# Sensors.net
KiCad netlist of a schematic drawn in Altium Designer
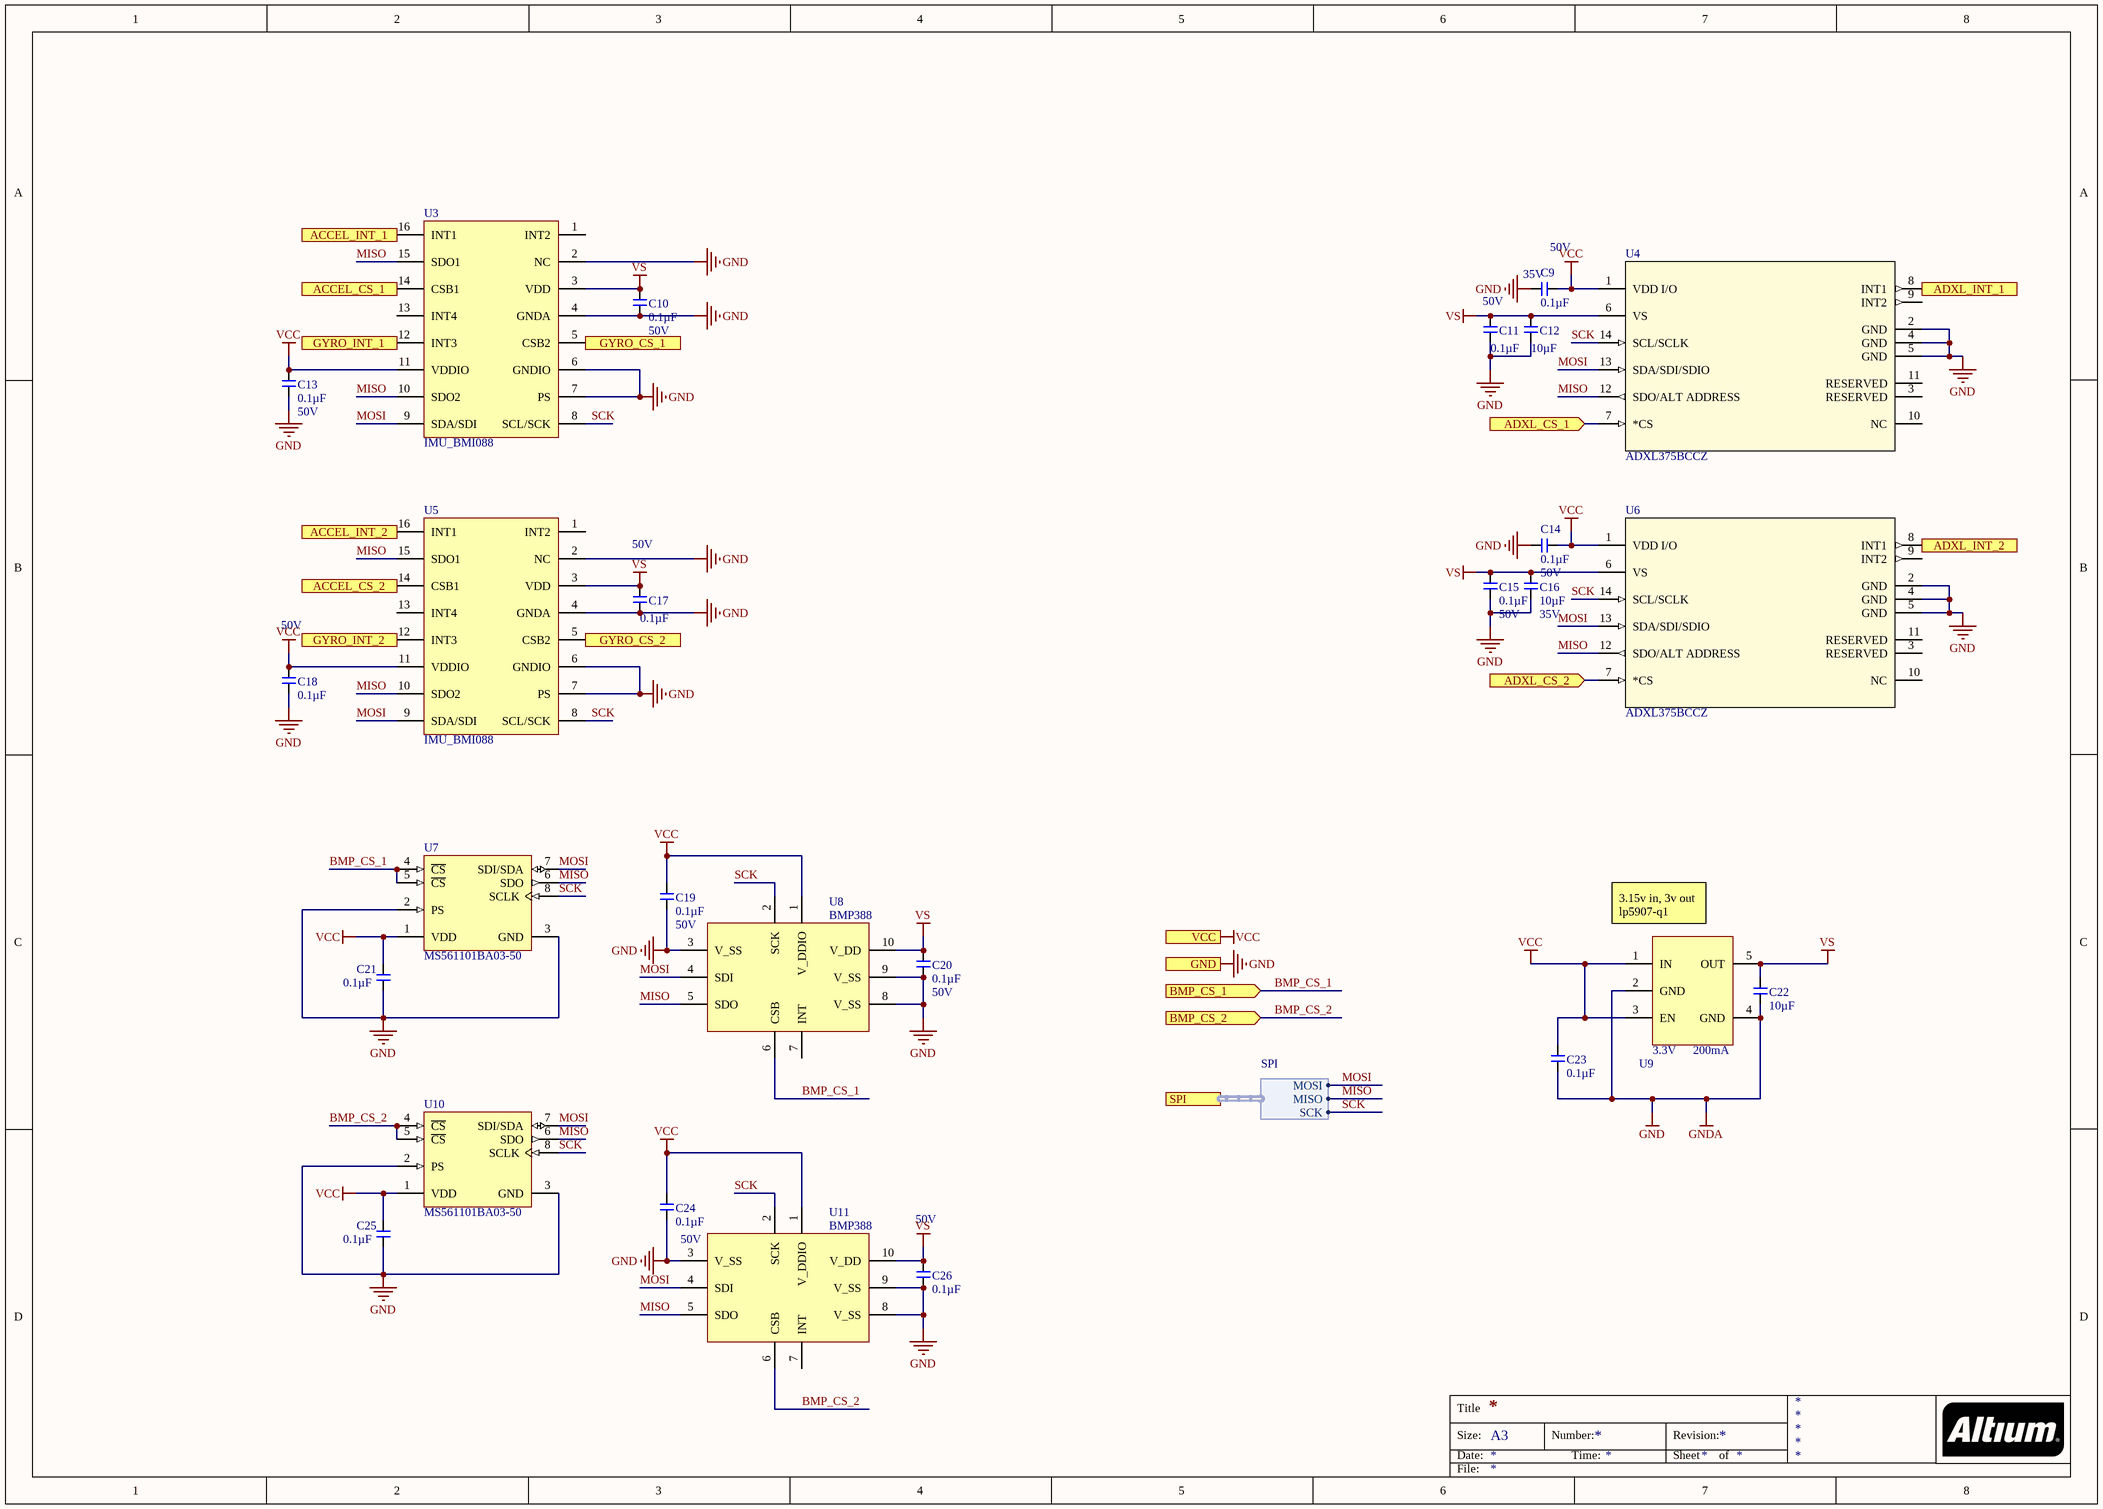
[diagram p0: Sensors.SchDoc]

(export (version "E")
  (design (tool "Eeschema 10.0.6"))
  (components
    (comp (ref "C9")
      (value "490-1519-1-ND")
      (footprint "C0603")
      (description "CAP CER 0603 0.1µF X7R 50V 10%")
      (fields
        (field (name "CAPACITANCE (SHORTHAND)") "0.1µF")
        (field (name "MANUFACTURER") "Murata Electronics North America")
        (field (name "RATED VOLTAGE") "50V")
      )
      (libsource (lib "Stanford Student Space Initiative") (part "__template_cap"))
    )
    (comp (ref "C10")
      (value "490-1519-1-ND")
      (footprint "C0603")
      (description "CAP CER 0603 0.1µF X7R 50V 10%")
      (fields
        (field (name "CAPACITANCE (SHORTHAND)") "0.1µF")
        (field (name "MANUFACTURER") "Murata Electronics North America")
        (field (name "RATED VOLTAGE") "50V")
      )
      (libsource (lib "Stanford Student Space Initiative") (part "__template_cap"))
    )
    (comp (ref "C11")
      (value "490-1519-1-ND")
      (footprint "C0603")
      (description "CAP CER 0603 0.1µF X7R 50V 10%")
      (fields
        (field (name "CAPACITANCE (SHORTHAND)") "0.1µF")
        (field (name "MANUFACTURER") "Murata Electronics North America")
        (field (name "RATED VOLTAGE") "50V")
      )
      (libsource (lib "Stanford Student Space Initiative") (part "__template_cap"))
    )
    (comp (ref "C12")
      (value "490-13248-1-ND")
      (footprint "C0603")
      (description "CAP CER 10UF 35V X5R 0603 20%")
      (fields
        (field (name "CAPACITANCE (SHORTHAND)") "10µF")
        (field (name "MANUFACTURER") "Murata Electronics North America")
        (field (name "RATED VOLTAGE") "35V")
      )
      (libsource (lib "Stanford Student Space Initiative") (part "__template_cap"))
    )
    (comp (ref "C13")
      (value "490-1519-1-ND")
      (footprint "C0603")
      (description "CAP CER 0603 0.1µF X7R 50V 10%")
      (fields
        (field (name "CAPACITANCE (SHORTHAND)") "0.1µF")
        (field (name "MANUFACTURER") "Murata Electronics North America")
        (field (name "RATED VOLTAGE") "50V")
      )
      (libsource (lib "Stanford Student Space Initiative") (part "__template_cap"))
    )
    (comp (ref "C14")
      (value "490-1519-1-ND")
      (footprint "C0603")
      (description "CAP CER 0603 0.1µF X7R 50V 10%")
      (fields
        (field (name "CAPACITANCE (SHORTHAND)") "0.1µF")
        (field (name "MANUFACTURER") "Murata Electronics North America")
        (field (name "RATED VOLTAGE") "50V")
      )
      (libsource (lib "Stanford Student Space Initiative") (part "__template_cap"))
    )
    (comp (ref "C15")
      (value "490-1519-1-ND")
      (footprint "C0603")
      (description "CAP CER 0603 0.1µF X7R 50V 10%")
      (fields
        (field (name "CAPACITANCE (SHORTHAND)") "0.1µF")
        (field (name "MANUFACTURER") "Murata Electronics North America")
        (field (name "RATED VOLTAGE") "50V")
      )
      (libsource (lib "Stanford Student Space Initiative") (part "__template_cap"))
    )
    (comp (ref "C16")
      (value "490-13248-1-ND")
      (footprint "C0603")
      (description "CAP CER 10UF 35V X5R 0603 20%")
      (fields
        (field (name "CAPACITANCE (SHORTHAND)") "10µF")
        (field (name "MANUFACTURER") "Murata Electronics North America")
        (field (name "RATED VOLTAGE") "35V")
      )
      (libsource (lib "Stanford Student Space Initiative") (part "__template_cap"))
    )
    (comp (ref "C17")
      (value "490-1519-1-ND")
      (footprint "C0603")
      (description "CAP CER 0603 0.1µF X7R 50V 10%")
      (fields
        (field (name "CAPACITANCE (SHORTHAND)") "0.1µF")
        (field (name "MANUFACTURER") "Murata Electronics North America")
        (field (name "RATED VOLTAGE") "50V")
      )
      (libsource (lib "Stanford Student Space Initiative") (part "__template_cap"))
    )
    (comp (ref "C18")
      (value "490-1519-1-ND")
      (footprint "C0603")
      (description "CAP CER 0603 0.1µF X7R 50V 10%")
      (fields
        (field (name "CAPACITANCE (SHORTHAND)") "0.1µF")
        (field (name "MANUFACTURER") "Murata Electronics North America")
        (field (name "RATED VOLTAGE") "50V")
      )
      (libsource (lib "Stanford Student Space Initiative") (part "__template_cap"))
    )
    (comp (ref "C19")
      (value "490-1519-1-ND")
      (footprint "C0603")
      (description "CAP CER 0603 0.1µF X7R 50V 10%")
      (fields
        (field (name "CAPACITANCE (SHORTHAND)") "0.1µF")
        (field (name "MANUFACTURER") "Murata Electronics North America")
        (field (name "RATED VOLTAGE") "50V")
      )
      (libsource (lib "Stanford Student Space Initiative") (part "__template_cap"))
    )
    (comp (ref "C20")
      (value "490-1519-1-ND")
      (footprint "C0603")
      (description "CAP CER 0603 0.1µF X7R 50V 10%")
      (fields
        (field (name "CAPACITANCE (SHORTHAND)") "0.1µF")
        (field (name "MANUFACTURER") "Murata Electronics North America")
        (field (name "RATED VOLTAGE") "50V")
      )
      (libsource (lib "Stanford Student Space Initiative") (part "__template_cap"))
    )
    (comp (ref "C21")
      (value "490-1519-1-ND")
      (footprint "C0603")
      (description "CAP CER 0603 0.1µF X7R 50V 10%")
      (fields
        (field (name "MANUFACTURER") "Murata Electronics North America")
        (field (name "CAPACITANCE (SHORTHAND)") "0.1µF")
      )
      (libsource (lib "Stanford Student Space Initiative") (part "__template_cap"))
    )
    (comp (ref "C22")
      (value "490-13248-1-ND")
      (footprint "C0603")
      (description "CAP CER 10UF 35V X5R 0603 20%")
      (fields
        (field (name "CAPACITANCE (SHORTHAND)") "10µF")
        (field (name "MANUFACTURER") "Murata Electronics North America")
      )
      (libsource (lib "Stanford Student Space Initiative") (part "__template_cap"))
    )
    (comp (ref "C23")
      (value "490-1519-1-ND")
      (footprint "C0603")
      (description "CAP CER 0603 0.1µF X7R 50V 10%")
      (fields
        (field (name "CAPACITANCE (SHORTHAND)") "0.1µF")
        (field (name "MANUFACTURER") "Murata Electronics North America")
      )
      (libsource (lib "Stanford Student Space Initiative") (part "__template_cap"))
    )
    (comp (ref "C24")
      (value "490-1519-1-ND")
      (footprint "C0603")
      (description "CAP CER 0603 0.1µF X7R 50V 10%")
      (fields
        (field (name "CAPACITANCE (SHORTHAND)") "0.1µF")
        (field (name "MANUFACTURER") "Murata Electronics North America")
        (field (name "RATED VOLTAGE") "50V")
      )
      (libsource (lib "Stanford Student Space Initiative") (part "__template_cap"))
    )
    (comp (ref "C25")
      (value "490-1519-1-ND")
      (footprint "C0603")
      (description "CAP CER 0603 0.1µF X7R 50V 10%")
      (fields
        (field (name "MANUFACTURER") "Murata Electronics North America")
        (field (name "CAPACITANCE (SHORTHAND)") "0.1µF")
      )
      (libsource (lib "Stanford Student Space Initiative") (part "__template_cap"))
    )
    (comp (ref "C26")
      (value "490-1519-1-ND")
      (footprint "C0603")
      (description "CAP CER 0603 0.1µF X7R 50V 10%")
      (fields
        (field (name "CAPACITANCE (SHORTHAND)") "0.1µF")
        (field (name "MANUFACTURER") "Murata Electronics North America")
        (field (name "RATED VOLTAGE") "50V")
      )
      (libsource (lib "Stanford Student Space Initiative") (part "__template_cap"))
    )
    (comp (ref "U3")
      (value "IMU_BMI088")
      (footprint "BMI088")
      (description "Bosch BMI088")
      (libsource (lib "Stanford Student Space Initiative") (part "IMU_BMI088"))
    )
    (comp (ref "U4")
      (value "ADXL375BCCZ")
      (footprint "LGA_CC-14-1")
      (description "200G Accelcerometer")
      (fields
        (field (name "MANUFACTURER") "Analog Devices")
        (field (name "MANUFACTURER PART NUMBER") "ADXL375BCCZ-RL7")
      )
      (libsource (lib "Stanford Student Space Initiative") (part "ADXL375BCCZ"))
    )
    (comp (ref "U5")
      (value "IMU_BMI088")
      (footprint "BMI088")
      (description "Bosch BMI088")
      (libsource (lib "Stanford Student Space Initiative") (part "IMU_BMI088"))
    )
    (comp (ref "U6")
      (value "ADXL375BCCZ")
      (footprint "LGA_CC-14-1")
      (description "200G Accelcerometer")
      (fields
        (field (name "MANUFACTURER") "Analog Devices")
        (field (name "MANUFACTURER PART NUMBER") "ADXL375BCCZ-RL7")
      )
      (libsource (lib "Stanford Student Space Initiative") (part "ADXL375BCCZ"))
    )
    (comp (ref "U7")
      (value "MS561101BA03-50")
      (footprint "MSI-MS561101BA03-50-8_V")
      (description "Pressure Sensor 1.44V to 3.6V 0.01bar to 1.2bar Absolute 8-Pin QFN T/R")
      (libsource (lib "Stanford Student Space Initiative") (part "MSI-MS561101BA03-50-8"))
    )
    (comp (ref "U8")
      (value "BMP388")
      (footprint "8 pin LGA")
      (description "SENSOR PRESSURE ABS")
      (fields (field (name "MANUFACTURER") "Bosch Sensortec"))
      (libsource (lib "Stanford Student Space Initiative") (part "BMP388"))
    )
    (comp (ref "U9")
      (value "LDO_TLV70033QDDCRQ1")
      (footprint "5SOT23")
      (description "IC REG LDO 3.3V .2A SOT23-5")
      (fields
        (field (name "MANUFACTURER") "Texas Instruments")
        (field (name "MANUFACTURER PART NUMBER") "TLV70033QDDCRQ1")
        (field (name "VOLTAGE - OUTPUT") "3.3V")
        (field (name "CURRENT - OUTPUT") "200mA")
      )
      (libsource (lib "Stanford Student Space Initiative") (part "LDO_TLV70033QDDCRQ1"))
    )
    (comp (ref "U10")
      (value "MS561101BA03-50")
      (footprint "MSI-MS561101BA03-50-8_V")
      (description "Pressure Sensor 1.44V to 3.6V 0.01bar to 1.2bar Absolute 8-Pin QFN T/R")
      (libsource (lib "Stanford Student Space Initiative") (part "MSI-MS561101BA03-50-8"))
    )
    (comp (ref "U11")
      (value "BMP388")
      (footprint "8 pin LGA")
      (description "SENSOR PRESSURE ABS")
      (fields (field (name "MANUFACTURER") "Bosch Sensortec"))
      (libsource (lib "Stanford Student Space Initiative") (part "BMP388"))
    )
  )
  (nets
    (net (code "2") (name "/ACCEL_CS_1") (class "Default")
      (node (ref "U3") (pin "14") (pinfunction "CSB1_14") (pintype "passive"))
    )
    (net (code "3") (name "/ACCEL_CS_2") (class "Default")
      (node (ref "U5") (pin "14") (pinfunction "CSB1_14") (pintype "passive"))
    )
    (net (code "4") (name "/ACCEL_INT_1") (class "Default")
      (node (ref "U3") (pin "16") (pinfunction "INT1_16") (pintype "passive"))
    )
    (net (code "5") (name "/ACCEL_INT_2") (class "Default")
      (node (ref "U5") (pin "16") (pinfunction "INT1_16") (pintype "passive"))
    )
    (net (code "6") (name "/ADXL_CS_1") (class "Default")
      (node (ref "U4") (pin "7") (pinfunction "*CS_7") (pintype "input"))
    )
    (net (code "7") (name "/ADXL_CS_2") (class "Default")
      (node (ref "U6") (pin "7") (pinfunction "*CS_7") (pintype "input"))
    )
    (net (code "8") (name "/ADXL_INT_1") (class "Default")
      (node (ref "U4") (pin "8") (pinfunction "INT1_8") (pintype "output"))
    )
    (net (code "9") (name "/ADXL_INT_2") (class "Default")
      (node (ref "U6") (pin "8") (pinfunction "INT1_8") (pintype "output"))
    )
    (net (code "10") (name "/BMP_CS_1") (class "Default")
      (node (ref "U7") (pin "4") (pinfunction "~{CS}_4") (pintype "input"))
      (node (ref "U7") (pin "5") (pinfunction "~{CS}_5") (pintype "input"))
      (node (ref "U8") (pin "6") (pinfunction "CSB_6") (pintype "passive"))
    )
    (net (code "11") (name "/BMP_CS_2") (class "Default")
      (node (ref "U10") (pin "4") (pinfunction "~{CS}_4") (pintype "input"))
      (node (ref "U10") (pin "5") (pinfunction "~{CS}_5") (pintype "input"))
      (node (ref "U11") (pin "6") (pinfunction "CSB_6") (pintype "passive"))
    )
    (net (code "12") (name "/GYRO_CS_1") (class "Default")
      (node (ref "U3") (pin "5") (pinfunction "CSB2_5") (pintype "passive"))
    )
    (net (code "13") (name "/GYRO_CS_2") (class "Default")
      (node (ref "U5") (pin "5") (pinfunction "CSB2_5") (pintype "passive"))
    )
    (net (code "14") (name "/GYRO_INT_1") (class "Default")
      (node (ref "U3") (pin "12") (pinfunction "INT3_12") (pintype "passive"))
    )
    (net (code "15") (name "/GYRO_INT_2") (class "Default")
      (node (ref "U5") (pin "12") (pinfunction "INT3_12") (pintype "passive"))
    )
    (net (code "16") (name "/MISO") (class "Default")
      (node (ref "U10") (pin "6") (pinfunction "SDO_6") (pintype "output"))
      (node (ref "U11") (pin "5") (pinfunction "SDO_5") (pintype "passive"))
      (node (ref "U3") (pin "10") (pinfunction "SDO2_10") (pintype "passive"))
      (node (ref "U3") (pin "15") (pinfunction "SDO1_15") (pintype "passive"))
      (node (ref "U4") (pin "12") (pinfunction "SDO/ALT_ADDRESS_12") (pintype "output"))
      (node (ref "U5") (pin "10") (pinfunction "SDO2_10") (pintype "passive"))
      (node (ref "U5") (pin "15") (pinfunction "SDO1_15") (pintype "passive"))
      (node (ref "U6") (pin "12") (pinfunction "SDO/ALT_ADDRESS_12") (pintype "output"))
      (node (ref "U7") (pin "6") (pinfunction "SDO_6") (pintype "output"))
      (node (ref "U8") (pin "5") (pinfunction "SDO_5") (pintype "passive"))
    )
    (net (code "17") (name "/MOSI") (class "Default")
      (node (ref "U10") (pin "7") (pinfunction "SDI/SDA_7") (pintype "bidirectional"))
      (node (ref "U11") (pin "4") (pinfunction "SDI_4") (pintype "passive"))
      (node (ref "U3") (pin "9") (pinfunction "SDA/SDI_9") (pintype "passive"))
      (node (ref "U4") (pin "13") (pinfunction "SDA/SDI/SDIO_13") (pintype "input"))
      (node (ref "U5") (pin "9") (pinfunction "SDA/SDI_9") (pintype "passive"))
      (node (ref "U6") (pin "13") (pinfunction "SDA/SDI/SDIO_13") (pintype "input"))
      (node (ref "U7") (pin "7") (pinfunction "SDI/SDA_7") (pintype "bidirectional"))
      (node (ref "U8") (pin "4") (pinfunction "SDI_4") (pintype "passive"))
    )
    (net (code "18") (name "/SCK") (class "Default")
      (node (ref "U10") (pin "8") (pinfunction "SCLK_8") (pintype "input"))
      (node (ref "U11") (pin "2") (pinfunction "SCK_2") (pintype "passive"))
      (node (ref "U3") (pin "8") (pinfunction "SCL/SCK_8") (pintype "passive"))
      (node (ref "U4") (pin "14") (pinfunction "SCL/SCLK_14") (pintype "input"))
      (node (ref "U5") (pin "8") (pinfunction "SCL/SCK_8") (pintype "passive"))
      (node (ref "U6") (pin "14") (pinfunction "SCL/SCLK_14") (pintype "input"))
      (node (ref "U7") (pin "8") (pinfunction "SCLK_8") (pintype "input"))
      (node (ref "U8") (pin "2") (pinfunction "SCK_2") (pintype "passive"))
    )
    (net (code "20") (name "GND") (class "Default")
      (node (ref "C10") (pin "2") (pintype "passive"))
      (node (ref "C11") (pin "1") (pintype "passive"))
      (node (ref "C12") (pin "2") (pintype "passive"))
      (node (ref "C13") (pin "2") (pintype "passive"))
      (node (ref "C14") (pin "2") (pintype "passive"))
      (node (ref "C15") (pin "1") (pintype "passive"))
      (node (ref "C16") (pin "2") (pintype "passive"))
      (node (ref "C17") (pin "2") (pintype "passive"))
      (node (ref "C18") (pin "2") (pintype "passive"))
      (node (ref "C19") (pin "2") (pintype "passive"))
      (node (ref "C20") (pin "2") (pintype "passive"))
      (node (ref "C21") (pin "2") (pintype "passive"))
      (node (ref "C22") (pin "2") (pintype "passive"))
      (node (ref "C23") (pin "2") (pintype "passive"))
      (node (ref "C24") (pin "2") (pintype "passive"))
      (node (ref "C25") (pin "2") (pintype "passive"))
      (node (ref "C26") (pin "2") (pintype "passive"))
      (node (ref "C9") (pin "2") (pintype "passive"))
      (node (ref "U10") (pin "2") (pinfunction "PS_2") (pintype "input"))
      (node (ref "U10") (pin "3") (pinfunction "GND_3") (pintype "power_in"))
      (node (ref "U11") (pin "3") (pinfunction "V_SS_3") (pintype "passive"))
      (node (ref "U11") (pin "8") (pinfunction "V_SS_8") (pintype "passive"))
      (node (ref "U11") (pin "9") (pinfunction "V_SS_9") (pintype "passive"))
      (node (ref "U3") (pin "2") (pinfunction "NC_2") (pintype "passive"))
      (node (ref "U3") (pin "4") (pinfunction "GNDA_4") (pintype "passive"))
      (node (ref "U3") (pin "6") (pinfunction "GNDIO_6") (pintype "passive"))
      (node (ref "U3") (pin "7") (pinfunction "PS_7") (pintype "passive"))
      (node (ref "U4") (pin "2") (pinfunction "GND_2") (pintype "power_in"))
      (node (ref "U4") (pin "4") (pinfunction "GND_4") (pintype "power_in"))
      (node (ref "U4") (pin "5") (pinfunction "GND_5") (pintype "power_in"))
      (node (ref "U5") (pin "2") (pinfunction "NC_2") (pintype "passive"))
      (node (ref "U5") (pin "4") (pinfunction "GNDA_4") (pintype "passive"))
      (node (ref "U5") (pin "6") (pinfunction "GNDIO_6") (pintype "passive"))
      (node (ref "U5") (pin "7") (pinfunction "PS_7") (pintype "passive"))
      (node (ref "U6") (pin "2") (pinfunction "GND_2") (pintype "power_in"))
      (node (ref "U6") (pin "4") (pinfunction "GND_4") (pintype "power_in"))
      (node (ref "U6") (pin "5") (pinfunction "GND_5") (pintype "power_in"))
      (node (ref "U7") (pin "2") (pinfunction "PS_2") (pintype "input"))
      (node (ref "U7") (pin "3") (pinfunction "GND_3") (pintype "power_in"))
      (node (ref "U8") (pin "3") (pinfunction "V_SS_3") (pintype "passive"))
      (node (ref "U8") (pin "8") (pinfunction "V_SS_8") (pintype "passive"))
      (node (ref "U8") (pin "9") (pinfunction "V_SS_9") (pintype "passive"))
      (node (ref "U9") (pin "2") (pinfunction "GND_2") (pintype "passive"))
      (node (ref "U9") (pin "4") (pinfunction "GND_4") (pintype "passive"))
    )
    (net (code "21") (name "VCC") (class "Default")
      (node (ref "C13") (pin "1") (pintype "passive"))
      (node (ref "C14") (pin "1") (pintype "passive"))
      (node (ref "C18") (pin "1") (pintype "passive"))
      (node (ref "C19") (pin "1") (pintype "passive"))
      (node (ref "C21") (pin "1") (pintype "passive"))
      (node (ref "C23") (pin "1") (pintype "passive"))
      (node (ref "C24") (pin "1") (pintype "passive"))
      (node (ref "C25") (pin "1") (pintype "passive"))
      (node (ref "C9") (pin "1") (pintype "passive"))
      (node (ref "U10") (pin "1") (pinfunction "VDD_1") (pintype "power_in"))
      (node (ref "U11") (pin "1") (pinfunction "V_DDIO_1") (pintype "passive"))
      (node (ref "U3") (pin "11") (pinfunction "VDDIO_11") (pintype "passive"))
      (node (ref "U4") (pin "1") (pinfunction "VDD_I/O_1") (pintype "power_in"))
      (node (ref "U5") (pin "11") (pinfunction "VDDIO_11") (pintype "passive"))
      (node (ref "U6") (pin "1") (pinfunction "VDD_I/O_1") (pintype "power_in"))
      (node (ref "U7") (pin "1") (pinfunction "VDD_1") (pintype "power_in"))
      (node (ref "U8") (pin "1") (pinfunction "V_DDIO_1") (pintype "passive"))
      (node (ref "U9") (pin "1") (pinfunction "IN_1") (pintype "passive"))
      (node (ref "U9") (pin "3") (pinfunction "EN_3") (pintype "passive"))
    )
    (net (code "22") (name "VS") (class "Default")
      (node (ref "C10") (pin "1") (pintype "passive"))
      (node (ref "C11") (pin "2") (pintype "passive"))
      (node (ref "C12") (pin "1") (pintype "passive"))
      (node (ref "C15") (pin "2") (pintype "passive"))
      (node (ref "C16") (pin "1") (pintype "passive"))
      (node (ref "C17") (pin "1") (pintype "passive"))
      (node (ref "C20") (pin "1") (pintype "passive"))
      (node (ref "C22") (pin "1") (pintype "passive"))
      (node (ref "C26") (pin "1") (pintype "passive"))
      (node (ref "U11") (pin "10") (pinfunction "V_DD_10") (pintype "passive"))
      (node (ref "U3") (pin "3") (pinfunction "VDD_3") (pintype "passive"))
      (node (ref "U4") (pin "6") (pinfunction "VS_6") (pintype "power_in"))
      (node (ref "U5") (pin "3") (pinfunction "VDD_3") (pintype "passive"))
      (node (ref "U6") (pin "6") (pinfunction "VS_6") (pintype "power_in"))
      (node (ref "U8") (pin "10") (pinfunction "V_DD_10") (pintype "passive"))
      (node (ref "U9") (pin "5") (pinfunction "OUT_5") (pintype "passive"))
    )
    (net (code "23") (name "unconnected-(U3-INT2-Pad1)") (class "Default")
      (node (ref "U3") (pin "1") (pinfunction "INT2_1") (pintype "passive"))
    )
    (net (code "24") (name "unconnected-(U3-INT4-Pad13)") (class "Default")
      (node (ref "U3") (pin "13") (pinfunction "INT4_13") (pintype "passive"))
    )
    (net (code "25") (name "unconnected-(U4-INT2-Pad9)") (class "Default")
      (node (ref "U4") (pin "9") (pinfunction "INT2_9") (pintype "output"))
    )
    (net (code "26") (name "unconnected-(U4-NC-Pad10)") (class "Default")
      (node (ref "U4") (pin "10") (pinfunction "NC_10") (pintype "passive"))
    )
    (net (code "27") (name "unconnected-(U4-RESERVED-Pad3)") (class "Default")
      (node (ref "U4") (pin "3") (pinfunction "RESERVED_3") (pintype "passive"))
    )
    (net (code "28") (name "unconnected-(U4-RESERVED-Pad11)") (class "Default")
      (node (ref "U4") (pin "11") (pinfunction "RESERVED_11") (pintype "passive"))
    )
    (net (code "29") (name "unconnected-(U5-INT2-Pad1)") (class "Default")
      (node (ref "U5") (pin "1") (pinfunction "INT2_1") (pintype "passive"))
    )
    (net (code "30") (name "unconnected-(U5-INT4-Pad13)") (class "Default")
      (node (ref "U5") (pin "13") (pinfunction "INT4_13") (pintype "passive"))
    )
    (net (code "31") (name "unconnected-(U6-INT2-Pad9)") (class "Default")
      (node (ref "U6") (pin "9") (pinfunction "INT2_9") (pintype "output"))
    )
    (net (code "32") (name "unconnected-(U6-NC-Pad10)") (class "Default")
      (node (ref "U6") (pin "10") (pinfunction "NC_10") (pintype "passive"))
    )
    (net (code "33") (name "unconnected-(U6-RESERVED-Pad3)") (class "Default")
      (node (ref "U6") (pin "3") (pinfunction "RESERVED_3") (pintype "passive"))
    )
    (net (code "34") (name "unconnected-(U6-RESERVED-Pad11)") (class "Default")
      (node (ref "U6") (pin "11") (pinfunction "RESERVED_11") (pintype "passive"))
    )
    (net (code "35") (name "unconnected-(U8-INT-Pad7)") (class "Default")
      (node (ref "U8") (pin "7") (pinfunction "INT_7") (pintype "passive"))
    )
    (net (code "36") (name "unconnected-(U11-INT-Pad7)") (class "Default")
      (node (ref "U11") (pin "7") (pinfunction "INT_7") (pintype "passive"))
    )
  )
)
